# Nestling_2_1_EXB_IO.net
KiCad netlist of a schematic drawn in Altium Designer
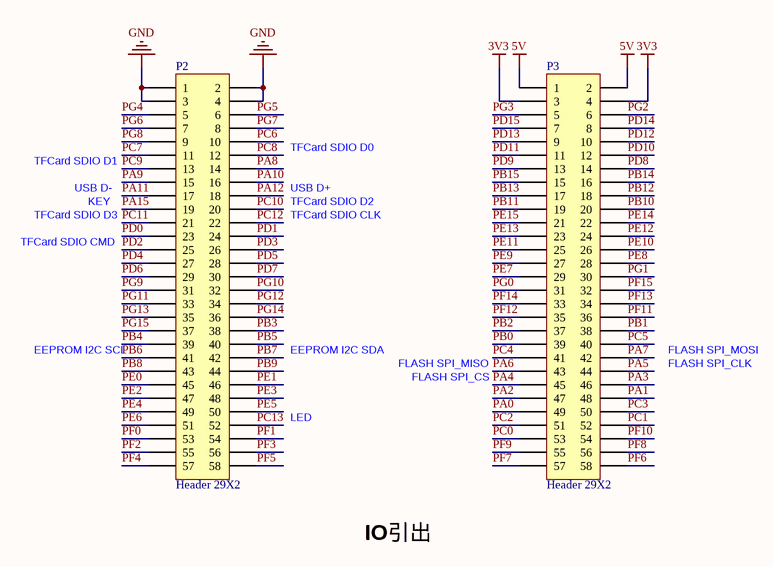
[diagram p0: Nestling_2.1_EXB_IO.SchDoc]

(export (version "E")
  (design (tool "Eeschema 10.0.6"))
  (components
    (comp (ref "P2")
      (value "Header 29X2")
      (footprint "HDR2X29")
      (libsource (lib "altium-import") (part "root_0_Header 29X2_"))
    )
    (comp (ref "P3")
      (value "Header 29X2")
      (footprint "HDR2X29")
      (libsource (lib "altium-import") (part "root_0_Header 29X2_"))
    )
  )
  (nets
    (net (code "1") (name "/PA0") (class "Default")
      (node (ref "P3") (pin "49") (pinfunction "49_49") (pintype "passive"))
    )
    (net (code "2") (name "/PA1") (class "Default")
      (node (ref "P3") (pin "48") (pinfunction "48_48") (pintype "passive"))
    )
    (net (code "3") (name "/PA2") (class "Default")
      (node (ref "P3") (pin "47") (pinfunction "47_47") (pintype "passive"))
    )
    (net (code "4") (name "/PA3") (class "Default")
      (node (ref "P3") (pin "46") (pinfunction "46_46") (pintype "passive"))
    )
    (net (code "5") (name "/PA4") (class "Default")
      (node (ref "P3") (pin "45") (pinfunction "45_45") (pintype "passive"))
    )
    (net (code "6") (name "/PA5") (class "Default")
      (node (ref "P3") (pin "44") (pinfunction "44_44") (pintype "passive"))
    )
    (net (code "7") (name "/PA6") (class "Default")
      (node (ref "P3") (pin "43") (pinfunction "43_43") (pintype "passive"))
    )
    (net (code "8") (name "/PA7") (class "Default")
      (node (ref "P3") (pin "42") (pinfunction "42_42") (pintype "passive"))
    )
    (net (code "9") (name "/PA8") (class "Default")
      (node (ref "P2") (pin "14") (pinfunction "14_14") (pintype "passive"))
    )
    (net (code "10") (name "/PA9") (class "Default")
      (node (ref "P2") (pin "15") (pinfunction "15_15") (pintype "passive"))
    )
    (net (code "11") (name "/PA10") (class "Default")
      (node (ref "P2") (pin "16") (pinfunction "16_16") (pintype "passive"))
    )
    (net (code "12") (name "/PA11") (class "Default")
      (node (ref "P2") (pin "17") (pinfunction "17_17") (pintype "passive"))
    )
    (net (code "13") (name "/PA12") (class "Default")
      (node (ref "P2") (pin "18") (pinfunction "18_18") (pintype "passive"))
    )
    (net (code "14") (name "/PA15") (class "Default")
      (node (ref "P2") (pin "19") (pinfunction "19_19") (pintype "passive"))
    )
    (net (code "15") (name "/PB0") (class "Default")
      (node (ref "P3") (pin "39") (pinfunction "39_39") (pintype "passive"))
    )
    (net (code "16") (name "/PB1") (class "Default")
      (node (ref "P3") (pin "38") (pinfunction "38_38") (pintype "passive"))
    )
    (net (code "17") (name "/PB2") (class "Default")
      (node (ref "P3") (pin "37") (pinfunction "37_37") (pintype "passive"))
    )
    (net (code "18") (name "/PB3") (class "Default")
      (node (ref "P2") (pin "38") (pinfunction "38_38") (pintype "passive"))
    )
    (net (code "19") (name "/PB4") (class "Default")
      (node (ref "P2") (pin "39") (pinfunction "39_39") (pintype "passive"))
    )
    (net (code "20") (name "/PB5") (class "Default")
      (node (ref "P2") (pin "40") (pinfunction "40_40") (pintype "passive"))
    )
    (net (code "21") (name "/PB6") (class "Default")
      (node (ref "P2") (pin "41") (pinfunction "41_41") (pintype "passive"))
    )
    (net (code "22") (name "/PB7") (class "Default")
      (node (ref "P2") (pin "42") (pinfunction "42_42") (pintype "passive"))
    )
    (net (code "23") (name "/PB8") (class "Default")
      (node (ref "P2") (pin "43") (pinfunction "43_43") (pintype "passive"))
    )
    (net (code "24") (name "/PB9") (class "Default")
      (node (ref "P2") (pin "44") (pinfunction "44_44") (pintype "passive"))
    )
    (net (code "25") (name "/PB10") (class "Default")
      (node (ref "P3") (pin "20") (pinfunction "20_20") (pintype "passive"))
    )
    (net (code "26") (name "/PB11") (class "Default")
      (node (ref "P3") (pin "19") (pinfunction "19_19") (pintype "passive"))
    )
    (net (code "27") (name "/PB12") (class "Default")
      (node (ref "P3") (pin "18") (pinfunction "18_18") (pintype "passive"))
    )
    (net (code "28") (name "/PB13") (class "Default")
      (node (ref "P3") (pin "17") (pinfunction "17_17") (pintype "passive"))
    )
    (net (code "29") (name "/PB14") (class "Default")
      (node (ref "P3") (pin "16") (pinfunction "16_16") (pintype "passive"))
    )
    (net (code "30") (name "/PB15") (class "Default")
      (node (ref "P3") (pin "15") (pinfunction "15_15") (pintype "passive"))
    )
    (net (code "31") (name "/PC0") (class "Default")
      (node (ref "P3") (pin "53") (pinfunction "53_53") (pintype "passive"))
    )
    (net (code "32") (name "/PC1") (class "Default")
      (node (ref "P3") (pin "52") (pinfunction "52_52") (pintype "passive"))
    )
    (net (code "33") (name "/PC2") (class "Default")
      (node (ref "P3") (pin "51") (pinfunction "51_51") (pintype "passive"))
    )
    (net (code "34") (name "/PC3") (class "Default")
      (node (ref "P3") (pin "50") (pinfunction "50_50") (pintype "passive"))
    )
    (net (code "35") (name "/PC4") (class "Default")
      (node (ref "P3") (pin "41") (pinfunction "41_41") (pintype "passive"))
    )
    (net (code "36") (name "/PC5") (class "Default")
      (node (ref "P3") (pin "40") (pinfunction "40_40") (pintype "passive"))
    )
    (net (code "37") (name "/PC6") (class "Default")
      (node (ref "P2") (pin "10") (pinfunction "10_10") (pintype "passive"))
    )
    (net (code "38") (name "/PC7") (class "Default")
      (node (ref "P2") (pin "11") (pinfunction "11_11") (pintype "passive"))
    )
    (net (code "39") (name "/PC8") (class "Default")
      (node (ref "P2") (pin "12") (pinfunction "12_12") (pintype "passive"))
    )
    (net (code "40") (name "/PC9") (class "Default")
      (node (ref "P2") (pin "13") (pinfunction "13_13") (pintype "passive"))
    )
    (net (code "41") (name "/PC10") (class "Default")
      (node (ref "P2") (pin "20") (pinfunction "20_20") (pintype "passive"))
    )
    (net (code "42") (name "/PC11") (class "Default")
      (node (ref "P2") (pin "21") (pinfunction "21_21") (pintype "passive"))
    )
    (net (code "43") (name "/PC12") (class "Default")
      (node (ref "P2") (pin "22") (pinfunction "22_22") (pintype "passive"))
    )
    (net (code "44") (name "/PC13") (class "Default")
      (node (ref "P2") (pin "52") (pinfunction "52_52") (pintype "passive"))
    )
    (net (code "45") (name "/PD0") (class "Default")
      (node (ref "P2") (pin "23") (pinfunction "23_23") (pintype "passive"))
    )
    (net (code "46") (name "/PD1") (class "Default")
      (node (ref "P2") (pin "24") (pinfunction "24_24") (pintype "passive"))
    )
    (net (code "47") (name "/PD2") (class "Default")
      (node (ref "P2") (pin "25") (pinfunction "25_25") (pintype "passive"))
    )
    (net (code "48") (name "/PD3") (class "Default")
      (node (ref "P2") (pin "26") (pinfunction "26_26") (pintype "passive"))
    )
    (net (code "49") (name "/PD4") (class "Default")
      (node (ref "P2") (pin "27") (pinfunction "27_27") (pintype "passive"))
    )
    (net (code "50") (name "/PD5") (class "Default")
      (node (ref "P2") (pin "28") (pinfunction "28_28") (pintype "passive"))
    )
    (net (code "51") (name "/PD6") (class "Default")
      (node (ref "P2") (pin "29") (pinfunction "29_29") (pintype "passive"))
    )
    (net (code "52") (name "/PD7") (class "Default")
      (node (ref "P2") (pin "30") (pinfunction "30_30") (pintype "passive"))
    )
    (net (code "53") (name "/PD8") (class "Default")
      (node (ref "P3") (pin "14") (pinfunction "14_14") (pintype "passive"))
    )
    (net (code "54") (name "/PD9") (class "Default")
      (node (ref "P3") (pin "13") (pinfunction "13_13") (pintype "passive"))
    )
    (net (code "55") (name "/PD10") (class "Default")
      (node (ref "P3") (pin "12") (pinfunction "12_12") (pintype "passive"))
    )
    (net (code "56") (name "/PD11") (class "Default")
      (node (ref "P3") (pin "11") (pinfunction "11_11") (pintype "passive"))
    )
    (net (code "57") (name "/PD12") (class "Default")
      (node (ref "P3") (pin "10") (pinfunction "10_10") (pintype "passive"))
    )
    (net (code "58") (name "/PD13") (class "Default")
      (node (ref "P3") (pin "9") (pinfunction "9_9") (pintype "passive"))
    )
    (net (code "59") (name "/PD14") (class "Default")
      (node (ref "P3") (pin "8") (pinfunction "8_8") (pintype "passive"))
    )
    (net (code "60") (name "/PD15") (class "Default")
      (node (ref "P3") (pin "7") (pinfunction "7_7") (pintype "passive"))
    )
    (net (code "61") (name "/PE0") (class "Default")
      (node (ref "P2") (pin "45") (pinfunction "45_45") (pintype "passive"))
    )
    (net (code "62") (name "/PE1") (class "Default")
      (node (ref "P2") (pin "46") (pinfunction "46_46") (pintype "passive"))
    )
    (net (code "63") (name "/PE2") (class "Default")
      (node (ref "P2") (pin "47") (pinfunction "47_47") (pintype "passive"))
    )
    (net (code "64") (name "/PE3") (class "Default")
      (node (ref "P2") (pin "48") (pinfunction "48_48") (pintype "passive"))
    )
    (net (code "65") (name "/PE4") (class "Default")
      (node (ref "P2") (pin "49") (pinfunction "49_49") (pintype "passive"))
    )
    (net (code "66") (name "/PE5") (class "Default")
      (node (ref "P2") (pin "50") (pinfunction "50_50") (pintype "passive"))
    )
    (net (code "67") (name "/PE6") (class "Default")
      (node (ref "P2") (pin "51") (pinfunction "51_51") (pintype "passive"))
    )
    (net (code "68") (name "/PE7") (class "Default")
      (node (ref "P3") (pin "29") (pinfunction "29_29") (pintype "passive"))
    )
    (net (code "69") (name "/PE8") (class "Default")
      (node (ref "P3") (pin "28") (pinfunction "28_28") (pintype "passive"))
    )
    (net (code "70") (name "/PE9") (class "Default")
      (node (ref "P3") (pin "27") (pinfunction "27_27") (pintype "passive"))
    )
    (net (code "71") (name "/PE10") (class "Default")
      (node (ref "P3") (pin "26") (pinfunction "26_26") (pintype "passive"))
    )
    (net (code "72") (name "/PE11") (class "Default")
      (node (ref "P3") (pin "25") (pinfunction "25_25") (pintype "passive"))
    )
    (net (code "73") (name "/PE12") (class "Default")
      (node (ref "P3") (pin "24") (pinfunction "24_24") (pintype "passive"))
    )
    (net (code "74") (name "/PE13") (class "Default")
      (node (ref "P3") (pin "23") (pinfunction "23_23") (pintype "passive"))
    )
    (net (code "75") (name "/PE14") (class "Default")
      (node (ref "P3") (pin "22") (pinfunction "22_22") (pintype "passive"))
    )
    (net (code "76") (name "/PE15") (class "Default")
      (node (ref "P3") (pin "21") (pinfunction "21_21") (pintype "passive"))
    )
    (net (code "77") (name "/PF0") (class "Default")
      (node (ref "P2") (pin "53") (pinfunction "53_53") (pintype "passive"))
    )
    (net (code "78") (name "/PF1") (class "Default")
      (node (ref "P2") (pin "54") (pinfunction "54_54") (pintype "passive"))
    )
    (net (code "79") (name "/PF2") (class "Default")
      (node (ref "P2") (pin "55") (pinfunction "55_55") (pintype "passive"))
    )
    (net (code "80") (name "/PF3") (class "Default")
      (node (ref "P2") (pin "56") (pinfunction "56_56") (pintype "passive"))
    )
    (net (code "81") (name "/PF4") (class "Default")
      (node (ref "P2") (pin "57") (pinfunction "57_57") (pintype "passive"))
    )
    (net (code "82") (name "/PF5") (class "Default")
      (node (ref "P2") (pin "58") (pinfunction "58_58") (pintype "passive"))
    )
    (net (code "83") (name "/PF6") (class "Default")
      (node (ref "P3") (pin "58") (pinfunction "58_58") (pintype "passive"))
    )
    (net (code "84") (name "/PF7") (class "Default")
      (node (ref "P3") (pin "57") (pinfunction "57_57") (pintype "passive"))
    )
    (net (code "85") (name "/PF8") (class "Default")
      (node (ref "P3") (pin "56") (pinfunction "56_56") (pintype "passive"))
    )
    (net (code "86") (name "/PF9") (class "Default")
      (node (ref "P3") (pin "55") (pinfunction "55_55") (pintype "passive"))
    )
    (net (code "87") (name "/PF10") (class "Default")
      (node (ref "P3") (pin "54") (pinfunction "54_54") (pintype "passive"))
    )
    (net (code "88") (name "/PF11") (class "Default")
      (node (ref "P3") (pin "36") (pinfunction "36_36") (pintype "passive"))
    )
    (net (code "89") (name "/PF12") (class "Default")
      (node (ref "P3") (pin "35") (pinfunction "35_35") (pintype "passive"))
    )
    (net (code "90") (name "/PF13") (class "Default")
      (node (ref "P3") (pin "34") (pinfunction "34_34") (pintype "passive"))
    )
    (net (code "91") (name "/PF14") (class "Default")
      (node (ref "P3") (pin "33") (pinfunction "33_33") (pintype "passive"))
    )
    (net (code "92") (name "/PF15") (class "Default")
      (node (ref "P3") (pin "32") (pinfunction "32_32") (pintype "passive"))
    )
    (net (code "93") (name "/PG0") (class "Default")
      (node (ref "P3") (pin "31") (pinfunction "31_31") (pintype "passive"))
    )
    (net (code "94") (name "/PG1") (class "Default")
      (node (ref "P3") (pin "30") (pinfunction "30_30") (pintype "passive"))
    )
    (net (code "95") (name "/PG2") (class "Default")
      (node (ref "P3") (pin "6") (pinfunction "6_6") (pintype "passive"))
    )
    (net (code "96") (name "/PG3") (class "Default")
      (node (ref "P3") (pin "5") (pinfunction "5_5") (pintype "passive"))
    )
    (net (code "97") (name "/PG4") (class "Default")
      (node (ref "P2") (pin "5") (pinfunction "5_5") (pintype "passive"))
    )
    (net (code "98") (name "/PG5") (class "Default")
      (node (ref "P2") (pin "6") (pinfunction "6_6") (pintype "passive"))
    )
    (net (code "99") (name "/PG6") (class "Default")
      (node (ref "P2") (pin "7") (pinfunction "7_7") (pintype "passive"))
    )
    (net (code "100") (name "/PG7") (class "Default")
      (node (ref "P2") (pin "8") (pinfunction "8_8") (pintype "passive"))
    )
    (net (code "101") (name "/PG8") (class "Default")
      (node (ref "P2") (pin "9") (pinfunction "9_9") (pintype "passive"))
    )
    (net (code "102") (name "/PG9") (class "Default")
      (node (ref "P2") (pin "31") (pinfunction "31_31") (pintype "passive"))
    )
    (net (code "103") (name "/PG10") (class "Default")
      (node (ref "P2") (pin "32") (pinfunction "32_32") (pintype "passive"))
    )
    (net (code "104") (name "/PG11") (class "Default")
      (node (ref "P2") (pin "33") (pinfunction "33_33") (pintype "passive"))
    )
    (net (code "105") (name "/PG12") (class "Default")
      (node (ref "P2") (pin "34") (pinfunction "34_34") (pintype "passive"))
    )
    (net (code "106") (name "/PG13") (class "Default")
      (node (ref "P2") (pin "35") (pinfunction "35_35") (pintype "passive"))
    )
    (net (code "107") (name "/PG14") (class "Default")
      (node (ref "P2") (pin "36") (pinfunction "36_36") (pintype "passive"))
    )
    (net (code "108") (name "/PG15") (class "Default")
      (node (ref "P2") (pin "37") (pinfunction "37_37") (pintype "passive"))
    )
    (net (code "109") (name "3V3") (class "Default")
      (node (ref "P3") (pin "3") (pinfunction "3_3") (pintype "passive"))
      (node (ref "P3") (pin "4") (pinfunction "4_4") (pintype "passive"))
    )
    (net (code "110") (name "5V") (class "Default")
      (node (ref "P3") (pin "1") (pinfunction "1_1") (pintype "passive"))
      (node (ref "P3") (pin "2") (pinfunction "2_2") (pintype "passive"))
    )
    (net (code "111") (name "GND") (class "Default")
      (node (ref "P2") (pin "1") (pinfunction "1_1") (pintype "passive"))
      (node (ref "P2") (pin "2") (pinfunction "2_2") (pintype "passive"))
      (node (ref "P2") (pin "3") (pinfunction "3_3") (pintype "passive"))
      (node (ref "P2") (pin "4") (pinfunction "4_4") (pintype "passive"))
    )
  )
)
